# daughterboard_ver4_1.net
KiCad netlist of a schematic drawn in EAGLE
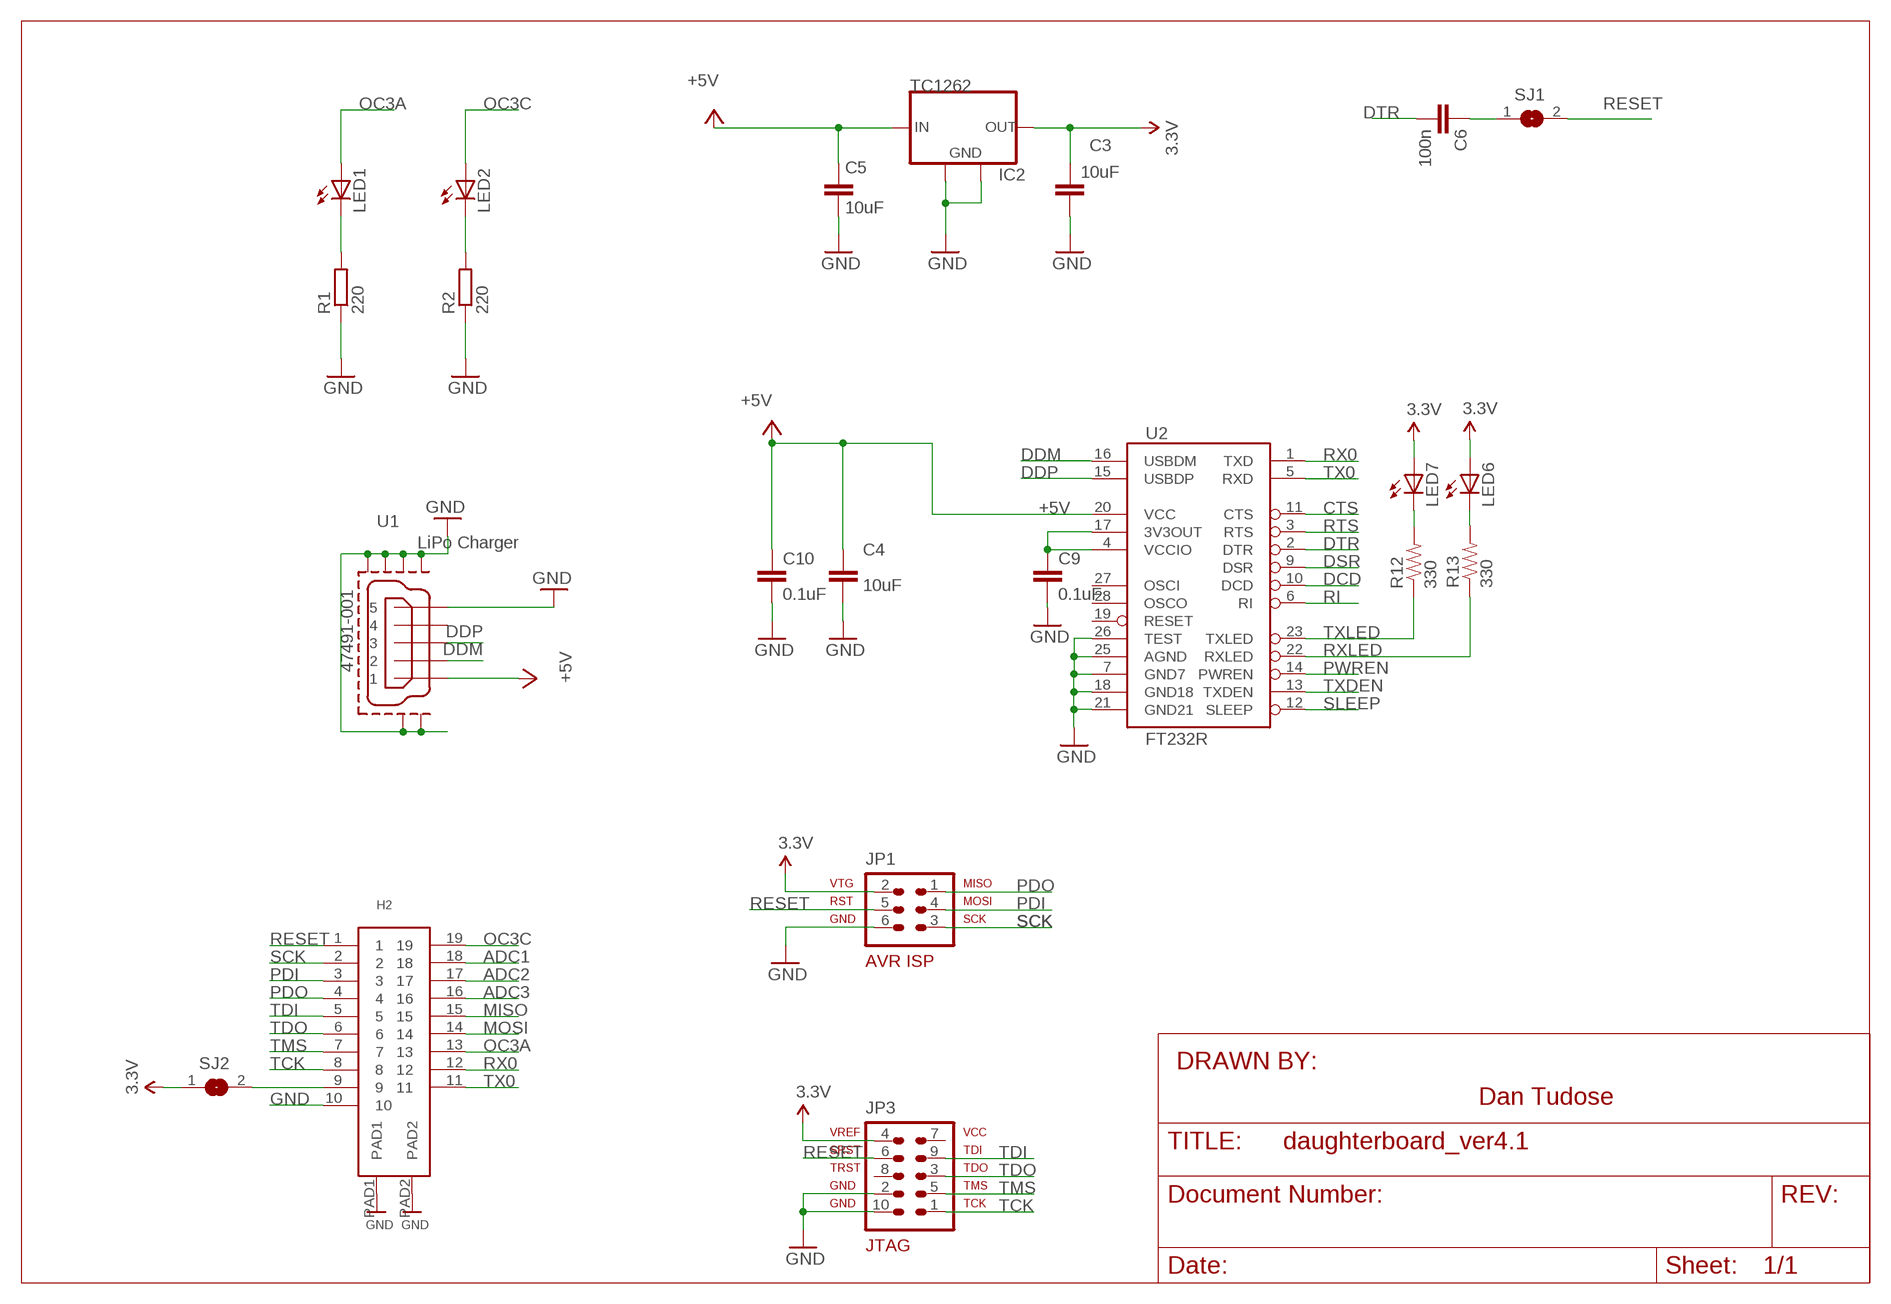
[diagram p0: schematic, sheet 1]

(export (version "E")
  (design (tool "Eeschema 10.0.6"))
  (components
    (comp (ref "C3")
      (value "10uF")
      (footprint "eagle-import:C0402")
      (libsource (lib "eagle-import") (part "C-EUC0402"))
    )
    (comp (ref "C4")
      (value "10uF")
      (footprint "eagle-import:C0402")
      (libsource (lib "eagle-import") (part "C-EUC0402"))
    )
    (comp (ref "C5")
      (value "10uF")
      (footprint "eagle-import:C0402")
      (libsource (lib "eagle-import") (part "C-EUC0402"))
    )
    (comp (ref "C6")
      (value "100n")
      (footprint "eagle-import:C0402")
      (libsource (lib "eagle-import") (part "C-EUC0402"))
    )
    (comp (ref "C9")
      (value "0.1uF")
      (footprint "eagle-import:0402-CAP")
      (libsource (lib "eagle-import") (part "CAP0402-CAP"))
    )
    (comp (ref "C10")
      (value "0.1uF")
      (footprint "eagle-import:0402-CAP")
      (libsource (lib "eagle-import") (part "CAP0402-CAP"))
    )
    (comp (ref "H2")
      (value "DF9-19P-1V(32)")
      (footprint "eagle-import:DF9-19P-1V(32)")
      (libsource (lib "eagle-import") (part "DF9-19P-1V(32)"))
    )
    (comp (ref "IC2")
      (value "TC1262")
      (footprint "eagle-import:SOT223")
      (libsource (lib "eagle-import") (part "MCP1825S-SOT223"))
    )
    (comp (ref "JP1")
      (value "AVR-ISP-6SMD")
      (footprint "eagle-import:2X3SMD")
      (libsource (lib "eagle-import") (part "AVR-ISP-6SMD"))
    )
    (comp (ref "JP3")
      (value "AVR-JTAG-10")
      (footprint "eagle-import:AVR-JTAG-10")
      (libsource (lib "eagle-import") (part "AVR-JTAG-10"))
    )
    (comp (ref "LED1")
      (value "LEDCHIPLED_0603")
      (footprint "eagle-import:CHIPLED_0603")
      (libsource (lib "eagle-import") (part "LEDCHIPLED_0603"))
    )
    (comp (ref "LED2")
      (value "LEDCHIPLED_0603")
      (footprint "eagle-import:CHIPLED_0603")
      (libsource (lib "eagle-import") (part "LEDCHIPLED_0603"))
    )
    (comp (ref "LED6")
      (value "LEDCHIP-LED0603")
      (footprint "eagle-import:CHIP-LED0603")
      (libsource (lib "eagle-import") (part "LEDCHIP-LED0603"))
    )
    (comp (ref "LED7")
      (value "LEDCHIP-LED0603")
      (footprint "eagle-import:CHIP-LED0603")
      (libsource (lib "eagle-import") (part "LEDCHIP-LED0603"))
    )
    (comp (ref "R1")
      (value "220")
      (footprint "eagle-import:R0402")
      (libsource (lib "eagle-import") (part "R-EU_R0402"))
    )
    (comp (ref "R2")
      (value "220")
      (footprint "eagle-import:R0402")
      (libsource (lib "eagle-import") (part "R-EU_R0402"))
    )
    (comp (ref "R12")
      (value "330")
      (footprint "eagle-import:0402-RES")
      (libsource (lib "eagle-import") (part "RESISTOR0402-RES"))
    )
    (comp (ref "R13")
      (value "330")
      (footprint "eagle-import:0402-RES")
      (libsource (lib "eagle-import") (part "RESISTOR0402-RES"))
    )
    (comp (ref "SJ1") (value "SJ") (footprint "eagle-import:SJ") (libsource (lib "eagle-import") (part "SJ")))
    (comp (ref "SJ2") (value "SJ") (footprint "eagle-import:SJ") (libsource (lib "eagle-import") (part "SJ")))
    (comp (ref "U1")
      (value "47491-001")
      (footprint "eagle-import:47491-0001")
      (libsource (lib "eagle-import") (part "47491-001"))
    )
    (comp (ref "U2")
      (value "FT232R")
      (footprint "eagle-import:SSOP28DB")
      (libsource (lib "eagle-import") (part "FT232RLSSOP"))
    )
  )
  (nets
    (net (code "1") (name "+5V") (class "Default")
      (node (ref "C10") (pin "1") (pinfunction "1_1") (pintype "passive"))
      (node (ref "C4") (pin "1") (pinfunction "1_1") (pintype "passive"))
      (node (ref "C5") (pin "1") (pinfunction "1_1") (pintype "passive"))
      (node (ref "IC2") (pin "1") (pinfunction "IN_1") (pintype "input"))
      (node (ref "U1") (pin "1") (pinfunction "1_1") (pintype "input"))
      (node (ref "U2") (pin "20") (pinfunction "VCC_20") (pintype "power_in"))
    )
    (net (code "2") (name "/ADC1") (class "Default")
      (node (ref "H2") (pin "18") (pinfunction "18_18") (pintype "bidirectional"))
    )
    (net (code "3") (name "/ADC2") (class "Default")
      (node (ref "H2") (pin "17") (pinfunction "17_17") (pintype "bidirectional"))
    )
    (net (code "4") (name "/ADC3") (class "Default")
      (node (ref "H2") (pin "16") (pinfunction "16_16") (pintype "bidirectional"))
    )
    (net (code "5") (name "/CTS") (class "Default")
      (node (ref "U2") (pin "11") (pinfunction "CTS_11") (pintype "input"))
    )
    (net (code "6") (name "/DCD") (class "Default")
      (node (ref "U2") (pin "10") (pinfunction "DCD_10") (pintype "input"))
    )
    (net (code "7") (name "/DDM") (class "Default")
      (node (ref "U1") (pin "2") (pinfunction "2_2") (pintype "input"))
      (node (ref "U2") (pin "16") (pinfunction "USBDM_16") (pintype "bidirectional"))
    )
    (net (code "8") (name "/DDP") (class "Default")
      (node (ref "U1") (pin "3") (pinfunction "3_3") (pintype "input"))
      (node (ref "U2") (pin "15") (pinfunction "USBDP_15") (pintype "bidirectional"))
    )
    (net (code "9") (name "/DSR") (class "Default")
      (node (ref "U2") (pin "9") (pinfunction "DSR_9") (pintype "input"))
    )
    (net (code "10") (name "/DTR") (class "Default")
      (node (ref "C6") (pin "2") (pinfunction "2_2") (pintype "passive"))
      (node (ref "U2") (pin "2") (pinfunction "DTR_2") (pintype "output"))
    )
    (net (code "11") (name "/MISO") (class "Default")
      (node (ref "H2") (pin "15") (pinfunction "15_15") (pintype "bidirectional"))
    )
    (net (code "12") (name "/MOSI") (class "Default")
      (node (ref "H2") (pin "14") (pinfunction "14_14") (pintype "bidirectional"))
    )
    (net (code "13") (name "/OC3A") (class "Default")
      (node (ref "H2") (pin "13") (pinfunction "13_13") (pintype "bidirectional"))
      (node (ref "LED1") (pin "A") (pinfunction "A_A") (pintype "passive"))
    )
    (net (code "14") (name "/OC3C") (class "Default")
      (node (ref "H2") (pin "19") (pinfunction "19_19") (pintype "bidirectional"))
      (node (ref "LED2") (pin "A") (pinfunction "A_A") (pintype "passive"))
    )
    (net (code "15") (name "/PDI") (class "Default")
      (node (ref "H2") (pin "3") (pinfunction "3_3") (pintype "bidirectional"))
      (node (ref "JP1") (pin "4") (pinfunction "4_4") (pintype "passive"))
    )
    (net (code "16") (name "/PDO") (class "Default")
      (node (ref "H2") (pin "4") (pinfunction "4_4") (pintype "bidirectional"))
      (node (ref "JP1") (pin "1") (pinfunction "1_1") (pintype "passive"))
    )
    (net (code "17") (name "/PWREN") (class "Default")
      (node (ref "U2") (pin "14") (pinfunction "PWREN_14") (pintype "input"))
    )
    (net (code "18") (name "/RESET") (class "Default")
      (node (ref "H2") (pin "1") (pinfunction "1_1") (pintype "bidirectional"))
      (node (ref "JP1") (pin "5") (pinfunction "5_5") (pintype "passive"))
      (node (ref "JP3") (pin "6") (pinfunction "6_6") (pintype "passive"))
      (node (ref "SJ1") (pin "2") (pinfunction "2_2") (pintype "passive"))
    )
    (net (code "19") (name "/RI") (class "Default")
      (node (ref "U2") (pin "6") (pinfunction "RI_6") (pintype "input"))
    )
    (net (code "20") (name "/RTS") (class "Default")
      (node (ref "U2") (pin "3") (pinfunction "RTS_3") (pintype "output"))
    )
    (net (code "21") (name "/RX0") (class "Default")
      (node (ref "H2") (pin "12") (pinfunction "12_12") (pintype "bidirectional"))
      (node (ref "U2") (pin "1") (pinfunction "TXD_1") (pintype "output"))
    )
    (net (code "22") (name "/RXLED") (class "Default")
      (node (ref "R13") (pin "1") (pinfunction "1_1") (pintype "passive"))
      (node (ref "U2") (pin "22") (pinfunction "RXLED_22") (pintype "input"))
    )
    (net (code "23") (name "/SCK") (class "Default")
      (node (ref "H2") (pin "2") (pinfunction "2_2") (pintype "bidirectional"))
      (node (ref "JP1") (pin "3") (pinfunction "3_3") (pintype "passive"))
    )
    (net (code "24") (name "/SLEEP") (class "Default")
      (node (ref "U2") (pin "12") (pinfunction "SLEEP_12") (pintype "input"))
    )
    (net (code "25") (name "/TCK") (class "Default")
      (node (ref "H2") (pin "8") (pinfunction "8_8") (pintype "bidirectional"))
      (node (ref "JP3") (pin "1") (pinfunction "1_1") (pintype "passive"))
    )
    (net (code "26") (name "/TDI") (class "Default")
      (node (ref "H2") (pin "5") (pinfunction "5_5") (pintype "bidirectional"))
      (node (ref "JP3") (pin "9") (pinfunction "9_9") (pintype "passive"))
    )
    (net (code "27") (name "/TDO") (class "Default")
      (node (ref "H2") (pin "6") (pinfunction "6_6") (pintype "bidirectional"))
      (node (ref "JP3") (pin "3") (pinfunction "3_3") (pintype "passive"))
    )
    (net (code "28") (name "/TMS") (class "Default")
      (node (ref "H2") (pin "7") (pinfunction "7_7") (pintype "bidirectional"))
      (node (ref "JP3") (pin "5") (pinfunction "5_5") (pintype "passive"))
    )
    (net (code "29") (name "/TX0") (class "Default")
      (node (ref "H2") (pin "11") (pinfunction "11_11") (pintype "bidirectional"))
      (node (ref "U2") (pin "5") (pinfunction "RXD_5") (pintype "input"))
    )
    (net (code "30") (name "/TXDEN") (class "Default")
      (node (ref "U2") (pin "13") (pinfunction "TXDEN_13") (pintype "input"))
    )
    (net (code "31") (name "/TXLED") (class "Default")
      (node (ref "R12") (pin "1") (pinfunction "1_1") (pintype "passive"))
      (node (ref "U2") (pin "23") (pinfunction "TXLED_23") (pintype "input"))
    )
    (net (code "32") (name "3.3V") (class "Default")
      (node (ref "C3") (pin "1") (pinfunction "1_1") (pintype "passive"))
      (node (ref "IC2") (pin "3") (pinfunction "OUT_3") (pintype "output"))
      (node (ref "JP1") (pin "2") (pinfunction "2_2") (pintype "passive"))
      (node (ref "JP3") (pin "4") (pinfunction "4_4") (pintype "passive"))
      (node (ref "LED6") (pin "A") (pinfunction "A_A") (pintype "passive"))
      (node (ref "LED7") (pin "A") (pinfunction "A_A") (pintype "passive"))
      (node (ref "SJ2") (pin "1") (pinfunction "1_1") (pintype "passive"))
    )
    (net (code "33") (name "GND") (class "Default")
      (node (ref "C10") (pin "2") (pinfunction "2_2") (pintype "passive"))
      (node (ref "C3") (pin "2") (pinfunction "2_2") (pintype "passive"))
      (node (ref "C4") (pin "2") (pinfunction "2_2") (pintype "passive"))
      (node (ref "C5") (pin "2") (pinfunction "2_2") (pintype "passive"))
      (node (ref "C9") (pin "2") (pinfunction "2_2") (pintype "passive"))
      (node (ref "H2") (pin "10") (pinfunction "10_10") (pintype "bidirectional"))
      (node (ref "H2") (pin "PAD1") (pinfunction "PAD1_PAD1") (pintype "bidirectional"))
      (node (ref "H2") (pin "PAD2") (pinfunction "PAD2_PAD2") (pintype "bidirectional"))
      (node (ref "IC2") (pin "2") (pinfunction "GND_2") (pintype "power_in"))
      (node (ref "IC2") (pin "4") (pinfunction "GND_4") (pintype "power_in"))
      (node (ref "JP1") (pin "6") (pinfunction "6_6") (pintype "passive"))
      (node (ref "JP3") (pin "10") (pinfunction "10_10") (pintype "passive"))
      (node (ref "JP3") (pin "2") (pinfunction "2_2") (pintype "passive"))
      (node (ref "R1") (pin "1") (pinfunction "1_1") (pintype "passive"))
      (node (ref "R2") (pin "1") (pinfunction "1_1") (pintype "passive"))
      (node (ref "U1") (pin "5") (pinfunction "5_5") (pintype "input"))
      (node (ref "U1") (pin "GND1") (pinfunction "GND1_GND1") (pintype "bidirectional"))
      (node (ref "U1") (pin "GND2") (pinfunction "GND2_GND2") (pintype "bidirectional"))
      (node (ref "U1") (pin "GND3") (pinfunction "GND3_GND3") (pintype "bidirectional"))
      (node (ref "U1") (pin "GND4") (pinfunction "GND4_GND4") (pintype "bidirectional"))
      (node (ref "U1") (pin "GND5") (pinfunction "GND5_GND5") (pintype "bidirectional"))
      (node (ref "U1") (pin "GND6") (pinfunction "GND6_GND6") (pintype "bidirectional"))
      (node (ref "U2") (pin "18") (pinfunction "GND18_18") (pintype "power_in"))
      (node (ref "U2") (pin "21") (pinfunction "GND21_21") (pintype "power_in"))
      (node (ref "U2") (pin "25") (pinfunction "AGND_25") (pintype "power_in"))
      (node (ref "U2") (pin "26") (pinfunction "TEST_26") (pintype "input"))
      (node (ref "U2") (pin "7") (pinfunction "GND7_7") (pintype "power_in"))
    )
    (net (code "34") (name "Net-(C6-Pad1)") (class "Default")
      (node (ref "C6") (pin "1") (pinfunction "1_1") (pintype "passive"))
      (node (ref "SJ1") (pin "1") (pinfunction "1_1") (pintype "passive"))
    )
    (net (code "35") (name "Net-(H2-Pad9)") (class "Default")
      (node (ref "H2") (pin "9") (pinfunction "9_9") (pintype "bidirectional"))
      (node (ref "SJ2") (pin "2") (pinfunction "2_2") (pintype "passive"))
    )
    (net (code "36") (name "Net-(LED1-PadC)") (class "Default")
      (node (ref "LED1") (pin "C") (pinfunction "C_C") (pintype "passive"))
      (node (ref "R1") (pin "2") (pinfunction "2_2") (pintype "passive"))
    )
    (net (code "37") (name "Net-(LED2-PadC)") (class "Default")
      (node (ref "LED2") (pin "C") (pinfunction "C_C") (pintype "passive"))
      (node (ref "R2") (pin "2") (pinfunction "2_2") (pintype "passive"))
    )
    (net (code "38") (name "Net-(LED6-PadC)") (class "Default")
      (node (ref "LED6") (pin "C") (pinfunction "C_C") (pintype "passive"))
      (node (ref "R13") (pin "2") (pinfunction "2_2") (pintype "passive"))
    )
    (net (code "39") (name "Net-(LED7-PadC)") (class "Default")
      (node (ref "LED7") (pin "C") (pinfunction "C_C") (pintype "passive"))
      (node (ref "R12") (pin "2") (pinfunction "2_2") (pintype "passive"))
    )
    (net (code "40") (name "Net-(U2-3V3OUT)") (class "Default")
      (node (ref "C9") (pin "1") (pinfunction "1_1") (pintype "passive"))
      (node (ref "U2") (pin "17") (pinfunction "3V3OUT_17") (pintype "output"))
      (node (ref "U2") (pin "4") (pinfunction "VCCIO_4") (pintype "power_in"))
    )
    (net (code "41") (name "unconnected-(JP3-Pad7)") (class "Default")
      (node (ref "JP3") (pin "7") (pinfunction "7_7") (pintype "passive"))
    )
    (net (code "42") (name "unconnected-(JP3-Pad8)") (class "Default")
      (node (ref "JP3") (pin "8") (pinfunction "8_8") (pintype "passive"))
    )
    (net (code "43") (name "unconnected-(U1-Pad4)") (class "Default")
      (node (ref "U1") (pin "4") (pinfunction "4_4") (pintype "input"))
    )
    (net (code "44") (name "unconnected-(U2-OSCI-Pad27)") (class "Default")
      (node (ref "U2") (pin "27") (pinfunction "OSCI_27") (pintype "input"))
    )
    (net (code "45") (name "unconnected-(U2-OSCO-Pad28)") (class "Default")
      (node (ref "U2") (pin "28") (pinfunction "OSCO_28") (pintype "output"))
    )
    (net (code "46") (name "unconnected-(U2-RESET-Pad19)") (class "Default")
      (node (ref "U2") (pin "19") (pinfunction "RESET_19") (pintype "input"))
    )
  )
)
